# FV1Buddy.net
KiCad netlist of a schematic drawn in Altium Designer
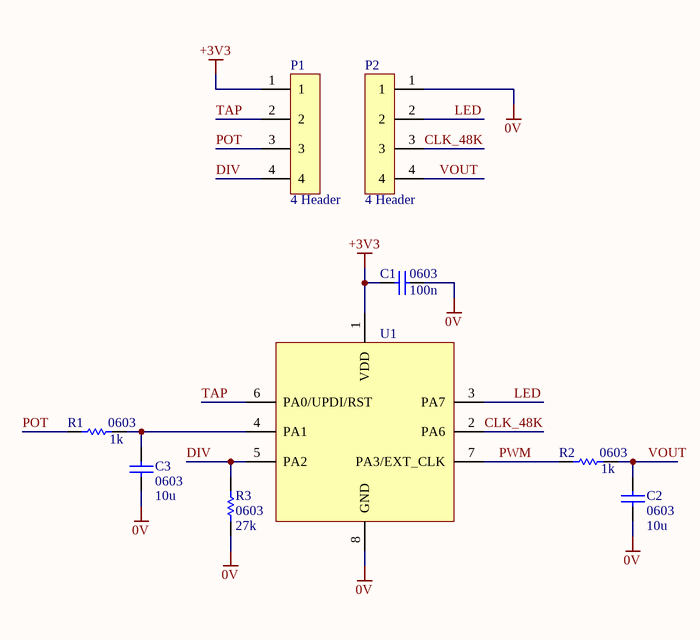
[diagram p0: FV1Buddy.SchDoc]

(export (version "E")
  (design (tool "Eeschema 10.0.6"))
  (components
    (comp (ref "C1")
      (value "100n")
      (footprint "CAPC1608X09N")
      (description "Generic 0603 Non Polarized Capacitor")
      (fields
        (field (name "PACKAGE") "0603")
        (field (name "MANUFACTURER") "Generic")
        (field (name "Comment") "C_NP_0603_Generic")
      )
      (libsource (lib "Altium Concord Pro on Altium 365") (part "C_NP"))
    )
    (comp (ref "C2")
      (value "10u")
      (footprint "CAPC1608X09N")
      (description "Generic 0603 Non Polarized Capacitor")
      (fields
        (field (name "PACKAGE") "0603")
        (field (name "MANUFACTURER") "Generic")
        (field (name "Comment") "C_NP_0603_Generic")
      )
      (libsource (lib "Altium Concord Pro on Altium 365") (part "C_NP"))
    )
    (comp (ref "C3")
      (value "10u")
      (footprint "CAPC1608X09N")
      (description "Generic 0603 Non Polarized Capacitor")
      (fields
        (field (name "PACKAGE") "0603")
        (field (name "MANUFACTURER") "Generic")
        (field (name "Comment") "C_NP_0603_Generic")
      )
      (libsource (lib "Altium Concord Pro on Altium 365") (part "C_NP"))
    )
    (comp (ref "P1") (value "4 Header") (footprint "H4") (libsource (lib "FV1Buddy") (part "H4")))
    (comp (ref "P2") (value "4 Header") (footprint "H4") (libsource (lib "") (part "H4_1")))
    (comp (ref "R1")
      (value "1k")
      (footprint "RESC1608X06N")
      (description "Generic 0603 Resistor")
      (fields
        (field (name "PACKAGE") "0603")
        (field (name "MANUFACTURER") "Generic")
        (field (name "Comment") "R_0603_Generic")
      )
      (libsource (lib "Altium Concord Pro on Altium 365") (part "R"))
    )
    (comp (ref "R2")
      (value "1k")
      (footprint "RESC1608X06N")
      (description "Generic 0603 Resistor")
      (fields
        (field (name "PACKAGE") "0603")
        (field (name "MANUFACTURER") "Generic")
        (field (name "Comment") "R_0603_Generic")
      )
      (libsource (lib "Altium Concord Pro on Altium 365") (part "R"))
    )
    (comp (ref "R3")
      (value "27k")
      (footprint "RESC1608X06N")
      (description "Generic 0603 Resistor")
      (fields
        (field (name "PACKAGE") "0603")
        (field (name "MANUFACTURER") "Generic")
        (field (name "Comment") "R_0603_Generic")
      )
      (libsource (lib "Altium Concord Pro on Altium 365") (part "R"))
    )
    (comp (ref "U1")
      (value "Attiny402")
      (footprint "SOIC127P600X175-8L")
      (libsource (lib "FV1Buddy") (part "Attiny402"))
    )
  )
  (nets
    (net (code "1") (name "+3V3") (class "Default")
      (node (ref "C1") (pin "1") (pinfunction "1_1") (pintype "passive"))
      (node (ref "P1") (pin "1") (pinfunction "1_1") (pintype "passive"))
      (node (ref "U1") (pin "1") (pinfunction "VDD_1") (pintype "passive"))
    )
    (net (code "2") (name "/CLK_48K") (class "Default")
      (node (ref "P2") (pin "3") (pinfunction "3_3") (pintype "passive"))
      (node (ref "U1") (pin "2") (pinfunction "PA6_2") (pintype "passive"))
    )
    (net (code "3") (name "/DIV") (class "Default")
      (node (ref "P1") (pin "4") (pinfunction "4_4") (pintype "passive"))
      (node (ref "R3") (pin "2") (pinfunction "2_2") (pintype "passive"))
      (node (ref "U1") (pin "5") (pinfunction "PA2_5") (pintype "passive"))
    )
    (net (code "4") (name "/LED") (class "Default")
      (node (ref "P2") (pin "2") (pinfunction "2_2") (pintype "passive"))
      (node (ref "U1") (pin "3") (pinfunction "PA7_3") (pintype "passive"))
    )
    (net (code "5") (name "/POT") (class "Default")
      (node (ref "P1") (pin "3") (pinfunction "3_3") (pintype "passive"))
      (node (ref "R1") (pin "1") (pinfunction "1_1") (pintype "passive"))
    )
    (net (code "6") (name "/PWM") (class "Default")
      (node (ref "R2") (pin "1") (pinfunction "1_1") (pintype "passive"))
      (node (ref "U1") (pin "7") (pinfunction "PA3/EXT_CLK_7") (pintype "passive"))
    )
    (net (code "7") (name "/TAP") (class "Default")
      (node (ref "P1") (pin "2") (pinfunction "2_2") (pintype "passive"))
      (node (ref "U1") (pin "6") (pinfunction "PA0/UPDI/RST_6") (pintype "passive"))
    )
    (net (code "8") (name "/VOUT") (class "Default")
      (node (ref "C2") (pin "2") (pinfunction "2_2") (pintype "passive"))
      (node (ref "P2") (pin "4") (pinfunction "4_4") (pintype "passive"))
      (node (ref "R2") (pin "2") (pinfunction "2_2") (pintype "passive"))
    )
    (net (code "9") (name "0V") (class "Default")
      (node (ref "C1") (pin "2") (pinfunction "2_2") (pintype "passive"))
      (node (ref "C2") (pin "1") (pinfunction "1_1") (pintype "passive"))
      (node (ref "C3") (pin "1") (pinfunction "1_1") (pintype "passive"))
      (node (ref "P2") (pin "1") (pinfunction "1_1") (pintype "passive"))
      (node (ref "R3") (pin "1") (pinfunction "1_1") (pintype "passive"))
      (node (ref "U1") (pin "8") (pinfunction "GND_8") (pintype "passive"))
    )
    (net (code "10") (name "Net-(U1-PA1)") (class "Default")
      (node (ref "C3") (pin "2") (pinfunction "2_2") (pintype "passive"))
      (node (ref "R1") (pin "2") (pinfunction "2_2") (pintype "passive"))
      (node (ref "U1") (pin "4") (pinfunction "PA1_4") (pintype "passive"))
    )
  )
)
